# Converter_PWM_to_Voltage.net
KiCad netlist of a schematic drawn in Altium Designer
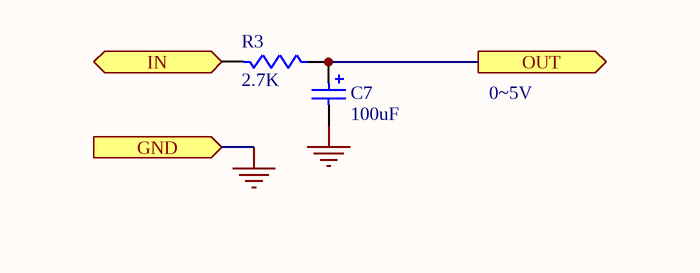
[diagram p0: Converter_PWM to Voltage.SchDoc]

(export (version "E")
  (design (tool "Eeschema 10.0.6"))
  (components
    (comp (ref "C7")
      (value "100uF")
      (footprint "CAPPR2.5-6.3x5")
      (description "Polarized Capacitor (Radial)")
      (fields
        (field (name "MANUFACTURER") "Generic Components")
        (field (name "Comment") "Capacitor")
        (field (name "PUBLISHER") "Altium Limited")
      )
      (libsource (lib "Miscellaneous Devices") (part "Cap Pol1"))
    )
    (comp (ref "R3")
      (value "2.7K")
      (footprint "AXIAL-0.4")
      (description "Resistor")
      (fields (field (name "MANUFACTURER") "Generic Components") (field (name "PUBLISHER") "Altium Limited"))
      (libsource (lib "Miscellaneous Devices") (part "Res1"))
    )
  )
  (nets
    (net (code "1") (name "/IN") (class "Default")
      (node (ref "R3") (pin "2") (pinfunction "2_2") (pintype "passive"))
    )
    (net (code "2") (name "/OUT") (class "Default")
      (node (ref "C7") (pin "1") (pinfunction "1_1") (pintype "passive"))
      (node (ref "R3") (pin "1") (pinfunction "1_1") (pintype "passive"))
    )
    (net (code "3") (name "GND") (class "Default")
      (node (ref "C7") (pin "2") (pinfunction "2_2") (pintype "passive"))
    )
  )
)
